# Buck-Converter.net
KiCad netlist of a schematic drawn in Altium Designer
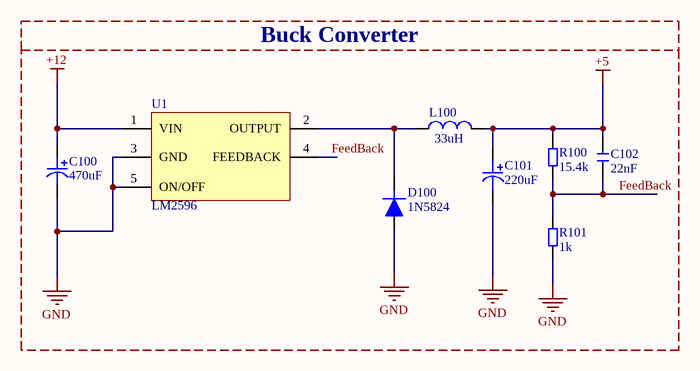
[diagram p0: Buck-Converter.SchDoc]

(export (version "E")
  (design (tool "Eeschema 10.0.6"))
  (components
    (comp (ref "C100")
      (value "470uF")
      (footprint "F981C475MMA")
      (description "Cap Tant Solid 100uF 63V M CASE 20%( 1.6 X 0.85 X 0.8mm) Inward L SMD 12 Ohm 125C T/R")
      (fields
        (field (name "MANUFACTURER") "Kyocera AVX")
        (field (name "MANUFACTURER PART NUMBER") "F981C475MMA")
      )
      (libsource (lib "Schematic-Lib-Zhrzkn") (part "CAP_0603_16V_Tantalum"))
    )
    (comp (ref "C101")
      (value "220uF")
      (footprint "F981C475MMA")
      (description "Cap Tant Solid 220uF 35V M CASE 20%( 1.6 X 0.85 X 0.8mm) Inward L SMD 12 Ohm 125C T/R")
      (fields
        (field (name "MANUFACTURER") "Kyocera AVX")
        (field (name "MANUFACTURER PART NUMBER") "F981C475MMA")
      )
      (libsource (lib "Schematic-Lib-Zhrzkn") (part "CAP_0603_16V_Tantalum"))
    )
    (comp (ref "C102")
      (value "22nF")
      (footprint "CAP-0402-X7R")
      (description "0402 100 nF 25 V ±10 % Tolerance X7R Surface Mount Multilayer Ceramic Capacitor")
      (fields
        (field (name "MANUFACTURER") "Kyocera AVX")
        (field (name "MANUFACTURER PART NUMBER") "04023C104KAT2A")
      )
      (libsource (lib "Schematic-Lib-Zhrzkn") (part "CAP-0402-X7R-0.1uF"))
    )
    (comp (ref "D100")
      (value "1N5824")
      (footprint "1N5824")
      (description "Diode Schottky 30V 5A 2-Pin Axial Leaded Tray")
      (fields (field (name "MANUFACTURER") "Microsemi"))
      (libsource (lib "Schematic-Lib-Zhrzkn") (part "1N5824"))
    )
    (comp (ref "L100")
      (value "33uH")
      (footprint "IND_0603")
      (libsource (lib "Schematic-Lib-Zhrzkn") (part "Inductor"))
    )
    (comp (ref "R100")
      (value "15.4k")
      (footprint "RES-0603")
      (description "贴片电阻 1000Ω ± 1.00% 0.1W ± 100ppm/℃ 0603")
      (fields
        (field (name "MANUFACTURER") "Vishay Dale")
        (field (name "MANUFACTURER PART NUMBER") "CRCW06031K00FKEA")
      )
      (libsource (lib "Schematic-Lib-Zhrzkn") (part "RES-0603-1k"))
    )
    (comp (ref "R101")
      (value "1k")
      (footprint "RES-0603")
      (description "贴片电阻 1000Ω ± 1.00% 0.1W ± 100ppm/℃ 0603")
      (fields
        (field (name "MANUFACTURER") "Vishay Dale")
        (field (name "MANUFACTURER PART NUMBER") "CRCW06031K00FKEA")
      )
      (libsource (lib "Schematic-Lib-Zhrzkn") (part "RES-0603-1k"))
    )
    (comp (ref "U1")
      (value "LM2596")
      (footprint "LM2596")
      (description "IC REG BUCK ADJ 3A TO263-5")
      (fields
        (field (name "MANUFACTURER") "TI National Semiconductor")
        (field (name "MANUFACTURER PART NUMBER") "LM2596SX-ADJ/NOPB")
      )
      (libsource (lib "Schematic-Lib-Zhrzkn") (part "LM2596"))
    )
  )
  (nets
    (net (code "1") (name "+5") (class "Default")
      (node (ref "C101") (pin "1") (pinfunction "1_1") (pintype "passive"))
      (node (ref "C102") (pin "2") (pinfunction "2_2") (pintype "passive"))
      (node (ref "L100") (pin "2") (pinfunction "2_2") (pintype "passive"))
      (node (ref "R100") (pin "2") (pinfunction "2_2") (pintype "passive"))
    )
    (net (code "2") (name "+12") (class "Default")
      (node (ref "C100") (pin "1") (pinfunction "1_1") (pintype "passive"))
      (node (ref "U1") (pin "1") (pinfunction "VIN_1") (pintype "passive"))
    )
    (net (code "3") (name "/FeedBack") (class "Default")
      (node (ref "C102") (pin "1") (pinfunction "1_1") (pintype "passive"))
      (node (ref "R100") (pin "1") (pinfunction "1_1") (pintype "passive"))
      (node (ref "R101") (pin "2") (pinfunction "2_2") (pintype "passive"))
      (node (ref "U1") (pin "4") (pinfunction "FEEDBACK_4") (pintype "passive"))
    )
    (net (code "4") (name "GND") (class "Default")
      (node (ref "C100") (pin "2") (pinfunction "2_2") (pintype "passive"))
      (node (ref "C101") (pin "2") (pinfunction "2_2") (pintype "passive"))
      (node (ref "D100") (pin "1") (pinfunction "1_1") (pintype "passive"))
      (node (ref "R101") (pin "1") (pinfunction "1_1") (pintype "passive"))
      (node (ref "U1") (pin "3") (pinfunction "GND_3") (pintype "passive"))
      (node (ref "U1") (pin "5") (pinfunction "ON/OFF_5") (pintype "passive"))
    )
    (net (code "5") (name "Net-(U1-OUTPUT)") (class "Default")
      (node (ref "D100") (pin "2") (pinfunction "2_2") (pintype "passive"))
      (node (ref "L100") (pin "1") (pinfunction "1_1") (pintype "passive"))
      (node (ref "U1") (pin "2") (pinfunction "OUTPUT_2") (pintype "passive"))
    )
  )
)
